# 03-POWER.net
KiCad netlist of a schematic drawn in Altium Designer
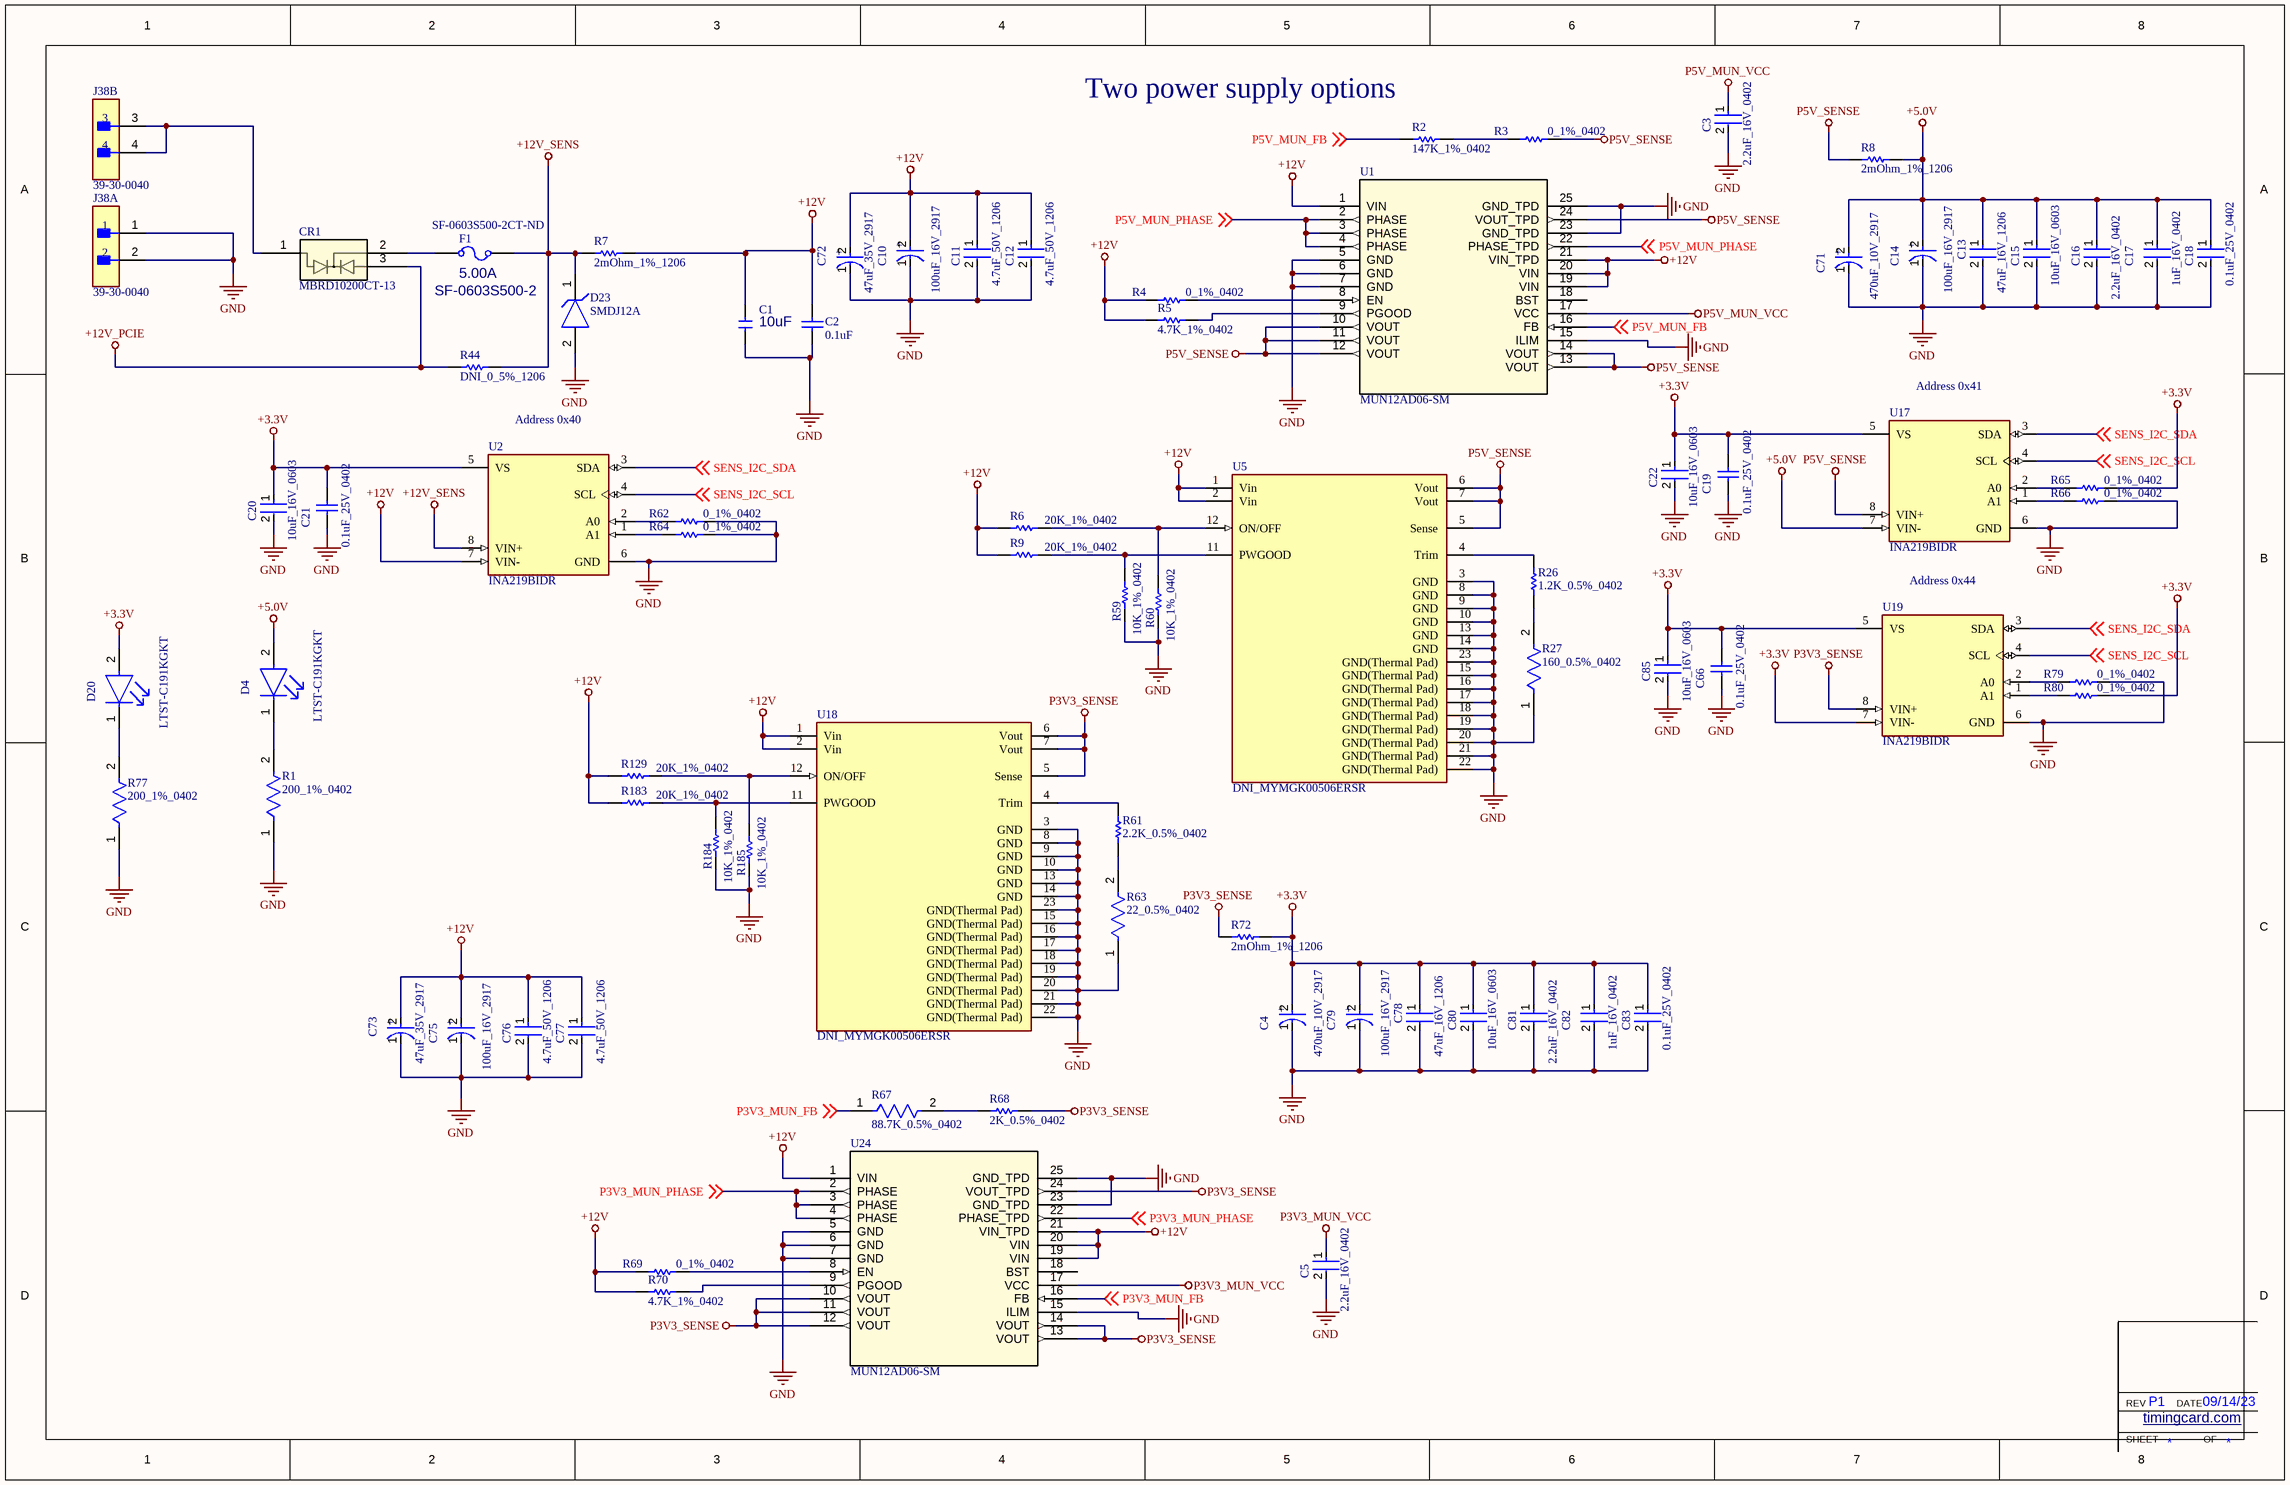
[diagram p0: 03-POWER.SchDoc]

(export (version "E")
  (design (tool "Eeschema 10.0.6"))
  (components
    (comp (ref "C1")
      (value "10uF")
      (footprint "CAPC2012X14N")
      (description "CAP, CER, 10.UF, 25V, 10%, X5R, 0805")
      (fields
        (field (name "MFG PART NUM") "TMK212BBJ106KG-T")
        (field (name "VALENTIUM PART NUM") "<VALENTIUM>")
      )
      (libsource (lib "Capacitors") (part "CAP_0805_10UF_25V"))
    )
    (comp (ref "C2")
      (value "0.1uF")
      (footprint "CAPC1608X87X45ML20T05")
      (description "C0603X104K5RACAUTO")
      (fields (field (name "MANUFACTURER") "Kemet"))
      (libsource (lib "Altium Content Vault") (part "CAP"))
    )
    (comp (ref "C3")
      (value "2.2uF_16V_0402")
      (footprint "FP-C1005-050-0_05-IPC_A")
      (description "Multilayer Ceramic Capacitors 2.2μF ±10% 16V X5R SMD 0402")
      (fields (field (name "TOLERANCE") "10%"))
      (libsource (lib "Altium Content Vault") (part "b4654b650e69147ec39a6b967a45e02"))
    )
    (comp (ref "C4")
      (value "470uF_10V_2917")
      (footprint "FP-TAJE-MFG")
      (description "470uF 10V  ±10% 500mΩ 2917  SMD Tantalum Capacitor")
      (fields (field (name "TOLERANCE") "10%") (field (name "VOLTAGE") "10V"))
      (libsource (lib "Altium Content Vault") (part "203bc49f2ac43e59fd269a8c329ed05"))
    )
    (comp (ref "C5")
      (value "2.2uF_16V_0402")
      (footprint "FP-C1005-050-0_05-IPC_A")
      (description "Multilayer Ceramic Capacitors 2.2μF ±10% 16V X5R SMD 0402")
      (fields (field (name "TOLERANCE") "10%"))
      (libsource (lib "Altium Content Vault") (part "b4654b650e69147ec39a6b967a45e02"))
    )
    (comp (ref "C10")
      (value "100uF_16V_2917")
      (footprint "FP-T495D107K016ATE125-MFG")
      (description "CAP TANT 100UF 10% 16V 2917")
      (fields (field (name "VOLTAGE") "16V") (field (name "TOLERANCE") "10%"))
      (libsource (lib "Altium Content Vault") (part "a00bbbee19879c290e62620ae7e47b1"))
    )
    (comp (ref "C11")
      (value "4.7uF_50V_1206")
      (footprint "FP-GRM31C-0_2-e0_3_0_8-IPC_C")
      (description "Chip Multilayer Ceramic Capacitors for General Purpose, 1206, 4.7uF, X7R, 15%, 10%, 50V")
      (fields (field (name "VOLTAGE") "50V") (field (name "TOLERANCE") "10%"))
      (libsource (lib "Altium Content Vault") (part "02cd4be3c70576c341d710602a673aa"))
    )
    (comp (ref "C12")
      (value "4.7uF_50V_1206")
      (footprint "FP-GRM31C-0_2-e0_3_0_8-IPC_C")
      (description "Chip Multilayer Ceramic Capacitors for General Purpose, 1206, 4.7uF, X7R, 15%, 10%, 50V")
      (fields (field (name "VOLTAGE") "50V") (field (name "TOLERANCE") "10%"))
      (libsource (lib "Altium Content Vault") (part "02cd4be3c70576c341d710602a673aa"))
    )
    (comp (ref "C13")
      (value "47uF_16V_1206")
      (footprint "FP-C3216-160-0_2-MFG")
      (description "Multilayer Ceramic Capacitors 47uF ±20% 16V X5R SMD 1206")
      (fields (field (name "TOLERANCE") "20%"))
      (libsource (lib "Altium Content Vault") (part "11868f565c42a9108669ba33697ecf6"))
    )
    (comp (ref "C14")
      (value "100uF_16V_2917")
      (footprint "FP-T495D107K016ATE125-MFG")
      (description "CAP TANT 100UF 10% 16V 2917")
      (fields (field (name "VOLTAGE") "16V") (field (name "TOLERANCE") "10%"))
      (libsource (lib "Altium Content Vault") (part "a00bbbee19879c290e62620ae7e47b1"))
    )
    (comp (ref "C15")
      (value "10uF_16V_0603")
      (footprint "FP-0603-L_1_6_0_2-W_0_8_0-MFG")
      (description "Multilayer Ceramic Capacitor 10uF 16V X5R 20% SMD 0603 T/R")
      (fields (field (name "TOLERANCE") "20%"))
      (libsource (lib "Altium Content Vault") (part "b4654b650e69147ec39a6b967a45e02"))
    )
    (comp (ref "C16")
      (value "2.2uF_16V_0402")
      (footprint "FP-C1005-050-0_05-IPC_A")
      (description "Multilayer Ceramic Capacitors 2.2μF ±10% 16V X5R SMD 0402")
      (fields (field (name "TOLERANCE") "10%"))
      (libsource (lib "Altium Content Vault") (part "b4654b650e69147ec39a6b967a45e02"))
    )
    (comp (ref "C17")
      (value "1uF_16V_0402")
      (footprint "FP-0402-L_1_0_0_05-W_0_5-IPC_A")
      (description "None")
      (fields (field (name "TOLERANCE") "10%"))
      (libsource (lib "Altium Content Vault") (part "b4654b650e69147ec39a6b967a45e02"))
    )
    (comp (ref "C18")
      (value "0.1uF_25V_0402")
      (footprint "FP-0402-L_1_0_1-W_0_5_0_1-IPC_C")
      (description "General Purpose Ceramic Capacitor, 0402, 100nF, 10%, X7R, 15%, 25V")
      (fields (field (name "VOLTAGE") "25V") (field (name "TOLERANCE") "10%"))
      (libsource (lib "Altium Content Vault") (part "b4654b650e69147ec39a6b967a45e02"))
    )
    (comp (ref "C19")
      (value "0.1uF_25V_0402")
      (footprint "CAPC1005X56X25NL10T15")
      (fields
        (field (name "PART NUMBER") "04023D104KAT2A")
        (field (name "MANUFACTURER") "AVX Interconnect / Elco")
      )
      (libsource (lib "Altium Content Vault") (part "CAP"))
    )
    (comp (ref "C20")
      (value "10uF_16V_0603")
      (footprint "FP-0603-L_1_6_0_2-W_0_8_0-MFG")
      (description "Multilayer Ceramic Capacitor 10uF 16V X5R 20% SMD 0603 T/R")
      (fields (field (name "TOLERANCE") "20%"))
      (libsource (lib "Altium Content Vault") (part "b4654b650e69147ec39a6b967a45e02"))
    )
    (comp (ref "C21")
      (value "0.1uF_25V_0402")
      (footprint "CAPC1005X56X25NL10T15")
      (fields
        (field (name "PART NUMBER") "04023D104KAT2A")
        (field (name "MANUFACTURER") "AVX Interconnect / Elco")
      )
      (libsource (lib "Altium Content Vault") (part "CAP"))
    )
    (comp (ref "C22")
      (value "10uF_16V_0603")
      (footprint "FP-0603-L_1_6_0_2-W_0_8_0-MFG")
      (description "Multilayer Ceramic Capacitor 10uF 16V X5R 20% SMD 0603 T/R")
      (fields (field (name "TOLERANCE") "20%"))
      (libsource (lib "Altium Content Vault") (part "b4654b650e69147ec39a6b967a45e02"))
    )
    (comp (ref "C66")
      (value "0.1uF_25V_0402")
      (footprint "CAPC1005X56X25NL10T15")
      (fields
        (field (name "PART NUMBER") "04023D104KAT2A")
        (field (name "MANUFACTURER") "AVX Interconnect / Elco")
      )
      (libsource (lib "Altium Content Vault") (part "CAP"))
    )
    (comp (ref "C71")
      (value "470uF_10V_2917")
      (footprint "FP-TAJE-MFG")
      (description "470uF 10V  ±10% 500mΩ 2917  SMD Tantalum Capacitor")
      (fields (field (name "TOLERANCE") "10%") (field (name "VOLTAGE") "10V"))
      (libsource (lib "Altium Content Vault") (part "203bc49f2ac43e59fd269a8c329ed05"))
    )
    (comp (ref "C72")
      (value "47uF_35V_2917")
      (footprint "FP-T521X476M035ATE030-MFG")
      (description "CAP TANT POLY 47UF 35V 2917")
      (fields (field (name "TOLERANCE") "20%"))
      (libsource (lib "Altium Content Vault") (part "a00bbbee19879c290e62620ae7e47b1"))
    )
    (comp (ref "C73")
      (value "47uF_35V_2917")
      (footprint "FP-T521X476M035ATE030-MFG")
      (description "CAP TANT POLY 47UF 35V 2917")
      (fields (field (name "TOLERANCE") "20%"))
      (libsource (lib "Altium Content Vault") (part "a00bbbee19879c290e62620ae7e47b1"))
    )
    (comp (ref "C75")
      (value "100uF_16V_2917")
      (footprint "FP-T495D107K016ATE125-MFG")
      (description "CAP TANT 100UF 10% 16V 2917")
      (fields (field (name "VOLTAGE") "16V") (field (name "TOLERANCE") "10%"))
      (libsource (lib "Altium Content Vault") (part "a00bbbee19879c290e62620ae7e47b1"))
    )
    (comp (ref "C76")
      (value "4.7uF_50V_1206")
      (footprint "FP-GRM31C-0_2-e0_3_0_8-IPC_C")
      (description "Chip Multilayer Ceramic Capacitors for General Purpose, 1206, 4.7uF, X7R, 15%, 10%, 50V")
      (fields (field (name "VOLTAGE") "50V") (field (name "TOLERANCE") "10%"))
      (libsource (lib "Altium Content Vault") (part "02cd4be3c70576c341d710602a673aa"))
    )
    (comp (ref "C77")
      (value "4.7uF_50V_1206")
      (footprint "FP-GRM31C-0_2-e0_3_0_8-IPC_C")
      (description "Chip Multilayer Ceramic Capacitors for General Purpose, 1206, 4.7uF, X7R, 15%, 10%, 50V")
      (fields (field (name "VOLTAGE") "50V") (field (name "TOLERANCE") "10%"))
      (libsource (lib "Altium Content Vault") (part "02cd4be3c70576c341d710602a673aa"))
    )
    (comp (ref "C78")
      (value "47uF_16V_1206")
      (footprint "FP-C3216-160-0_2-MFG")
      (description "Multilayer Ceramic Capacitors 47uF ±20% 16V X5R SMD 1206")
      (fields (field (name "TOLERANCE") "20%"))
      (libsource (lib "Altium Content Vault") (part "11868f565c42a9108669ba33697ecf6"))
    )
    (comp (ref "C79")
      (value "100uF_16V_2917")
      (footprint "FP-T495D107K016ATE125-MFG")
      (description "CAP TANT 100UF 10% 16V 2917")
      (fields (field (name "VOLTAGE") "16V") (field (name "TOLERANCE") "10%"))
      (libsource (lib "Altium Content Vault") (part "a00bbbee19879c290e62620ae7e47b1"))
    )
    (comp (ref "C80")
      (value "10uF_16V_0603")
      (footprint "FP-0603-L_1_6_0_2-W_0_8_0-MFG")
      (description "Multilayer Ceramic Capacitor 10uF 16V X5R 20% SMD 0603 T/R")
      (fields (field (name "TOLERANCE") "20%"))
      (libsource (lib "Altium Content Vault") (part "b4654b650e69147ec39a6b967a45e02"))
    )
    (comp (ref "C81")
      (value "2.2uF_16V_0402")
      (footprint "FP-C1005-050-0_05-IPC_A")
      (description "Multilayer Ceramic Capacitors 2.2μF ±10% 16V X5R SMD 0402")
      (fields (field (name "TOLERANCE") "10%"))
      (libsource (lib "Altium Content Vault") (part "b4654b650e69147ec39a6b967a45e02"))
    )
    (comp (ref "C82")
      (value "1uF_16V_0402")
      (footprint "FP-0402-L_1_0_0_05-W_0_5-IPC_A")
      (description "None")
      (fields (field (name "TOLERANCE") "10%"))
      (libsource (lib "Altium Content Vault") (part "b4654b650e69147ec39a6b967a45e02"))
    )
    (comp (ref "C83")
      (value "0.1uF_25V_0402")
      (footprint "FP-0402-L_1_0_1-W_0_5_0_1-IPC_C")
      (description "General Purpose Ceramic Capacitor, 0402, 100nF, 10%, X7R, 15%, 25V")
      (fields (field (name "VOLTAGE") "25V") (field (name "TOLERANCE") "10%"))
      (libsource (lib "Altium Content Vault") (part "b4654b650e69147ec39a6b967a45e02"))
    )
    (comp (ref "C85")
      (value "10uF_16V_0603")
      (footprint "FP-0603-L_1_6_0_2-W_0_8_0-MFG")
      (description "Multilayer Ceramic Capacitor 10uF 16V X5R 20% SMD 0603 T/R")
      (fields (field (name "TOLERANCE") "20%"))
      (libsource (lib "Altium Content Vault") (part "b4654b650e69147ec39a6b967a45e02"))
    )
    (comp (ref "CR1")
      (value "MBRD10200CT-13")
      (footprint "TO252(DPAK)_DIO")
      (description "No Description Available")
      (libsource (lib "MBRD10200CT-13") (part "MBRD10200CT-13"))
    )
    (comp (ref "D4")
      (value "LTST-C191KGKT")
      (footprint "FP-LTST-C191KGKT-MFG")
      (description "LED GREEN CLEAR SMD")
      (libsource (lib "Altium Content Vault") (part "8706943c75ba83719d021d2fdc84c58"))
    )
    (comp (ref "D20")
      (value "LTST-C191KGKT")
      (footprint "FP-LTST-C191KGKT-MFG")
      (description "LED GREEN CLEAR SMD")
      (libsource (lib "Altium Content Vault") (part "8706943c75ba83719d021d2fdc84c58"))
    )
    (comp (ref "D23")
      (value "SMDJ12A")
      (footprint "FP-DO-214AB_SMC_J-Bend-MFG")
      (description "TVS DIODE 12V 19.9V DO214AB")
      (libsource (lib "Altium Content Vault") (part "673ecd2ea4d7fb87b4005b0cb348b7d"))
    )
    (comp (ref "F1")
      (value "5.00A")
      (footprint "FUSM1608X60N")
      (description "FUSE SLOW 5.00A 32V M 0603")
      (fields
        (field (name "MFG PART NUM") "SF-0603S500-2")
        (field (name "VALENTIUM PART NUM") "<VALENTIUM>")
        (field (name "SUPPLIER PART NUMBER 1") "SF-0603S500-2CT-ND")
        (field (name "Comment") "FUSE_0603_5.00A")
      )
      (libsource (lib "Passives") (part "FUSE_0603_2.00A"))
    )
    (comp (ref "J38")
      (value "39-30-0040")
      (footprint "FP-39-30-0040-MFG")
      (description "CONN HEADER R/A 4POS 4.2MM")
      (fields
        (field (name "OCTOPART") "https://octopart.com/39-30-0040-molex-277428")
        (field (name "MANUFACTURER") "Molex")
      )
      (libsource (lib "Altium Content Vault") (part "ac72c5313ea981db199dbd0e8237b04"))
    )
    (comp (ref "R1")
      (value "200_1%_0402")
      (footprint "FP-ERJ2RK-IPC_A")
      (description "RES SMD 200 OHM 1% 1/10W 0402")
      (fields (field (name "TOLERANCE") "1%"))
      (libsource (lib "Altium Content Vault") (part "1029c3af85768c4190bb7ad29bc67b5"))
    )
    (comp (ref "R2")
      (value "147K_1%_0402")
      (footprint "RESC1005X40X25ML05T10")
      (fields (field (name "MANUFACTURER") "Yageo / Phycomp") (field (name "PART NUMBER") "RC0402FR-07147KL"))
      (libsource (lib "Altium Content Vault") (part "RES"))
    )
    (comp (ref "R3")
      (value "0_1%_0402")
      (footprint "RESC1005X40X25LL05T05")
      (description "Chip Resistor, 0 Ohm, 0.1 W, -55 to 155 degC, 0402 (1005 Metric), RoHS, Tape and Reel")
      (fields (field (name "MANUFACTURER") "Panasonic") (field (name "TOLERANCE") "5%"))
      (libsource (lib "Altium Content Vault") (part "RES-2"))
    )
    (comp (ref "R4")
      (value "0_1%_0402")
      (footprint "RESC1005X40X25LL05T05")
      (description "Chip Resistor, 0 Ohm, 0.1 W, -55 to 155 degC, 0402 (1005 Metric), RoHS, Tape and Reel")
      (fields (field (name "MANUFACTURER") "Panasonic") (field (name "TOLERANCE") "5%"))
      (libsource (lib "Altium Content Vault") (part "RES-2"))
    )
    (comp (ref "R5")
      (value "4.7K_1%_0402")
      (footprint "RESC1005X40X25NL10T10")
      (fields (field (name "MANUFACTURER") "Bourns") (field (name "PART NUMBER") "CR0402-FX-4701GLF"))
      (libsource (lib "Altium Content Vault") (part "RES"))
    )
    (comp (ref "R6")
      (value "20K_1%_0402")
      (footprint "RESC1005X40X25NL10T10")
      (fields (field (name "PART NUMBER") "MC00625W0402120K") (field (name "MANUFACTURER") "Multicomp"))
      (libsource (lib "Altium Content Vault") (part "RES"))
    )
    (comp (ref "R7")
      (value "2mOhm_1%_1206")
      (footprint "RESC3216X89X64NL25T25")
      (fields (field (name "MANUFACTURER") "Vishay Dale") (field (name "PART NUMBER") "WSL12062L000FEA18"))
      (libsource (lib "Altium Content Vault") (part "RES"))
    )
    (comp (ref "R8")
      (value "2mOhm_1%_1206")
      (footprint "RESC3216X89X64NL25T25")
      (fields (field (name "MANUFACTURER") "Vishay Dale") (field (name "PART NUMBER") "WSL12062L000FEA18"))
      (libsource (lib "Altium Content Vault") (part "RES"))
    )
    (comp (ref "R9")
      (value "20K_1%_0402")
      (footprint "RESC1005X40X25NL10T10")
      (fields (field (name "PART NUMBER") "MC00625W0402120K") (field (name "MANUFACTURER") "Multicomp"))
      (libsource (lib "Altium Content Vault") (part "RES"))
    )
    (comp (ref "R26")
      (value "1.2K_0.5%_0402")
      (footprint "RESC1005X40X25ML10T10")
      (fields (field (name "PART NUMBER") "ERA-2AED122X") (field (name "MANUFACTURER") "Panasonic"))
      (libsource (lib "Altium Content Vault") (part "RES"))
    )
    (comp (ref "R27")
      (value "160_0.5%_0402")
      (footprint "FP-RT0402-MFG")
      (description "RES SMD 160 OHM 0.5% 1/16W 0402")
      (fields
        (field (name "TOLERANCE") "0.005")
        (field (name "OCTOPART") "https://octopart.com/rt0402dre07160rl-yageo-1216058")
      )
      (libsource (lib "Altium Content Vault") (part "1029c3af85768c4190bb7ad29bc67b5"))
    )
    (comp (ref "R44")
      (value "DNI_0_5%_1206")
      (footprint "RESC3116X65X50ML20T20")
      (fields (field (name "PART NUMBER") "CRCW12060000Z0EAHP") (field (name "MANUFACTURER") "Vishay Dale"))
      (libsource (lib "Altium Content Vault") (part "RES"))
    )
    (comp (ref "R59")
      (value "10K_1%_0402")
      (footprint "RESC1005X40X25NL10T10")
      (fields (field (name "MANUFACTURER") "Bourns") (field (name "PART NUMBER") "CR0402-FX-1002GLF"))
      (libsource (lib "Altium Content Vault") (part "RES"))
    )
    (comp (ref "R60")
      (value "10K_1%_0402")
      (footprint "RESC1005X40X25NL10T10")
      (fields (field (name "MANUFACTURER") "Bourns") (field (name "PART NUMBER") "CR0402-FX-1002GLF"))
      (libsource (lib "Altium Content Vault") (part "RES"))
    )
    (comp (ref "R61")
      (value "2.2K_0.5%_0402")
      (footprint "RESC1005X40X25ML10T10")
      (fields (field (name "PART NUMBER") "ERA-2AED222X") (field (name "MANUFACTURER") "Panasonic"))
      (libsource (lib "Altium Content Vault") (part "RES"))
    )
    (comp (ref "R62")
      (value "0_1%_0402")
      (footprint "RESC1005X40X25LL05T05")
      (description "Chip Resistor, 0 Ohm, 0.1 W, -55 to 155 degC, 0402 (1005 Metric), RoHS, Tape and Reel")
      (fields (field (name "MANUFACTURER") "Panasonic") (field (name "TOLERANCE") "5%"))
      (libsource (lib "Altium Content Vault") (part "RES-2"))
    )
    (comp (ref "R63")
      (value "22_0.5%_0402")
      (footprint "FP-RG1005-IPC_A")
      (description "Automotive Metal Thin Film Chip Resistor, 0402, 22Ω, 0.5%, 100ppm/°C, 0.0625W, 75V")
      (fields (field (name "TOLERANCE") "0.5%"))
      (libsource (lib "Altium Content Vault") (part "1029c3af85768c4190bb7ad29bc67b5"))
    )
    (comp (ref "R64")
      (value "0_1%_0402")
      (footprint "RESC1005X40X25LL05T05")
      (description "Chip Resistor, 0 Ohm, 0.1 W, -55 to 155 degC, 0402 (1005 Metric), RoHS, Tape and Reel")
      (fields (field (name "MANUFACTURER") "Panasonic") (field (name "TOLERANCE") "5%"))
      (libsource (lib "Altium Content Vault") (part "RES-2"))
    )
    (comp (ref "R65")
      (value "0_1%_0402")
      (footprint "RESC1005X40X25LL05T05")
      (description "Chip Resistor, 0 Ohm, 0.1 W, -55 to 155 degC, 0402 (1005 Metric), RoHS, Tape and Reel")
      (fields (field (name "MANUFACTURER") "Panasonic") (field (name "TOLERANCE") "5%"))
      (libsource (lib "Altium Content Vault") (part "RES-2"))
    )
    (comp (ref "R66")
      (value "0_1%_0402")
      (footprint "RESC1005X40X25LL05T05")
      (description "Chip Resistor, 0 Ohm, 0.1 W, -55 to 155 degC, 0402 (1005 Metric), RoHS, Tape and Reel")
      (fields (field (name "MANUFACTURER") "Panasonic") (field (name "TOLERANCE") "5%"))
      (libsource (lib "Altium Content Vault") (part "RES-2"))
    )
    (comp (ref "R67")
      (value "88.7K_0.5%_0402")
      (footprint "FP-RT0402-MFG")
      (description "RES SMD 88.7K OHM 0.5% 1/16W")
      (fields
        (field (name "OCTOPART") "https://octopart.com/rt0402dre0788k7l-yageo-1439224")
        (field (name "MANUFACTURER") "Yageo")
      )
      (libsource (lib "Altium Content Vault") (part "1029c3af85768c4190bb7ad29bc67b5"))
    )
    (comp (ref "R68")
      (value "2K_0.5%_0402")
      (footprint "RESC1005X35X25LL10T10")
      (fields (field (name "PART NUMBER") "RT0402DRD072KL") (field (name "MANUFACTURER") "Yageo"))
      (libsource (lib "Altium Content Vault") (part "RES"))
    )
    (comp (ref "R69")
      (value "0_1%_0402")
      (footprint "RESC1005X40X25LL05T05")
      (description "Chip Resistor, 0 Ohm, 0.1 W, -55 to 155 degC, 0402 (1005 Metric), RoHS, Tape and Reel")
      (fields (field (name "MANUFACTURER") "Panasonic") (field (name "TOLERANCE") "5%"))
      (libsource (lib "Altium Content Vault") (part "RES-2"))
    )
    (comp (ref "R70")
      (value "4.7K_1%_0402")
      (footprint "RESC1005X40X25NL10T10")
      (fields (field (name "MANUFACTURER") "Bourns") (field (name "PART NUMBER") "CR0402-FX-4701GLF"))
      (libsource (lib "Altium Content Vault") (part "RES"))
    )
    (comp (ref "R72")
      (value "2mOhm_1%_1206")
      (footprint "RESC3216X89X64NL25T25")
      (fields (field (name "MANUFACTURER") "Vishay Dale") (field (name "PART NUMBER") "WSL12062L000FEA18"))
      (libsource (lib "Altium Content Vault") (part "RES"))
    )
    (comp (ref "R77")
      (value "200_1%_0402")
      (footprint "FP-ERJ2RK-IPC_A")
      (description "RES SMD 200 OHM 1% 1/10W 0402")
      (fields (field (name "TOLERANCE") "1%"))
      (libsource (lib "Altium Content Vault") (part "1029c3af85768c4190bb7ad29bc67b5"))
    )
    (comp (ref "R79")
      (value "0_1%_0402")
      (footprint "RESC1005X40X25LL05T05")
      (description "Chip Resistor, 0 Ohm, 0.1 W, -55 to 155 degC, 0402 (1005 Metric), RoHS, Tape and Reel")
      (fields (field (name "MANUFACTURER") "Panasonic") (field (name "TOLERANCE") "5%"))
      (libsource (lib "Altium Content Vault") (part "RES-2"))
    )
    (comp (ref "R80")
      (value "0_1%_0402")
      (footprint "RESC1005X40X25LL05T05")
      (description "Chip Resistor, 0 Ohm, 0.1 W, -55 to 155 degC, 0402 (1005 Metric), RoHS, Tape and Reel")
      (fields (field (name "MANUFACTURER") "Panasonic") (field (name "TOLERANCE") "5%"))
      (libsource (lib "Altium Content Vault") (part "RES-2"))
    )
    (comp (ref "R129")
      (value "20K_1%_0402")
      (footprint "RESC1005X40X25NL10T10")
      (fields (field (name "PART NUMBER") "MC00625W0402120K") (field (name "MANUFACTURER") "Multicomp"))
      (libsource (lib "Altium Content Vault") (part "RES"))
    )
    (comp (ref "R183")
      (value "20K_1%_0402")
      (footprint "RESC1005X40X25NL10T10")
      (fields (field (name "PART NUMBER") "MC00625W0402120K") (field (name "MANUFACTURER") "Multicomp"))
      (libsource (lib "Altium Content Vault") (part "RES"))
    )
    (comp (ref "R184")
      (value "10K_1%_0402")
      (footprint "RESC1005X40X25NL10T10")
      (fields (field (name "MANUFACTURER") "Bourns") (field (name "PART NUMBER") "CR0402-FX-1002GLF"))
      (libsource (lib "Altium Content Vault") (part "RES"))
    )
    (comp (ref "R185")
      (value "10K_1%_0402")
      (footprint "RESC1005X40X25NL10T10")
      (fields (field (name "MANUFACTURER") "Bourns") (field (name "PART NUMBER") "CR0402-FX-1002GLF"))
      (libsource (lib "Altium Content Vault") (part "RES"))
    )
    (comp (ref "U1")
      (value "MUN12AD06-SM")
      (footprint "MUN12AD06-SM_CYN")
      (description "No Description Available")
      (libsource (lib "MUN12AD06-SM") (part "MUN12AD06-SM"))
    )
    (comp (ref "U2")
      (value "INA219BIDR")
      (footprint "FP-D0008A-MFG")
      (description "IC MONITOR PWR/CURR BIDIR 8-SOIC")
      (libsource (lib "Altium Content Vault") (part "41cc1aee4cbc9fa2660a15773fa0e79"))
    )
    (comp (ref "U5")
      (value "DNI_MYMGK00506ERSR")
      (footprint "FP-MYMGK-12-MFG")
      (description "DC DC CONVERTER 0.7-5V")
      (libsource (lib "Altium Content Vault") (part "57b8017c1ce60d7b1362a625e7a4ba1"))
    )
    (comp (ref "U17")
      (value "INA219BIDR")
      (footprint "FP-D0008A-MFG")
      (description "IC MONITOR PWR/CURR BIDIR 8-SOIC")
      (libsource (lib "Altium Content Vault") (part "41cc1aee4cbc9fa2660a15773fa0e79"))
    )
    (comp (ref "U18")
      (value "DNI_MYMGK00506ERSR")
      (footprint "FP-MYMGK-12-MFG")
      (description "DC DC CONVERTER 0.7-5V")
      (libsource (lib "Altium Content Vault") (part "57b8017c1ce60d7b1362a625e7a4ba1"))
    )
    (comp (ref "U19")
      (value "INA219BIDR")
      (footprint "FP-D0008A-MFG")
      (description "IC MONITOR PWR/CURR BIDIR 8-SOIC")
      (libsource (lib "Altium Content Vault") (part "41cc1aee4cbc9fa2660a15773fa0e79"))
    )
    (comp (ref "U24")
      (value "MUN12AD06-SM")
      (footprint "MUN12AD06-SM_CYN")
      (description "No Description Available")
      (libsource (lib "MUN12AD06-SM") (part "MUN12AD06-SM"))
    )
  )
  (nets
    (net (code "1") (name "+3.3V") (class "Default")
      (node (ref "C19") (pin "2") (pinfunction "2_2") (pintype "passive"))
      (node (ref "C20") (pin "1") (pinfunction "1_1") (pintype "passive"))
      (node (ref "C21") (pin "2") (pinfunction "2_2") (pintype "passive"))
      (node (ref "C22") (pin "1") (pinfunction "1_1") (pintype "passive"))
      (node (ref "C4") (pin "2") (pinfunction "A_2") (pintype "passive"))
      (node (ref "C66") (pin "2") (pinfunction "2_2") (pintype "passive"))
      (node (ref "C78") (pin "1") (pinfunction "1_1") (pintype "passive"))
      (node (ref "C79") (pin "2") (pinfunction "A_2") (pintype "passive"))
      (node (ref "C80") (pin "1") (pinfunction "1_1") (pintype "passive"))
      (node (ref "C81") (pin "1") (pinfunction "1_1") (pintype "passive"))
      (node (ref "C82") (pin "1") (pinfunction "1_1") (pintype "passive"))
      (node (ref "C83") (pin "1") (pinfunction "1_1") (pintype "passive"))
      (node (ref "C85") (pin "1") (pinfunction "1_1") (pintype "passive"))
      (node (ref "D20") (pin "2") (pinfunction "A_2") (pintype "passive"))
      (node (ref "R65") (pin "2") (pinfunction "2_2") (pintype "passive"))
      (node (ref "R72") (pin "2") (pinfunction "2_2") (pintype "passive"))
      (node (ref "R80") (pin "2") (pinfunction "2_2") (pintype "passive"))
      (node (ref "U17") (pin "5") (pinfunction "VS_5") (pintype "power_in"))
      (node (ref "U19") (pin "5") (pinfunction "VS_5") (pintype "power_in"))
      (node (ref "U19") (pin "7") (pinfunction "VIN-_7") (pintype "input"))
      (node (ref "U2") (pin "5") (pinfunction "VS_5") (pintype "power_in"))
    )
    (net (code "2") (name "+5.0V") (class "Default")
      (node (ref "C13") (pin "1") (pinfunction "1_1") (pintype "passive"))
      (node (ref "C14") (pin "2") (pinfunction "A_2") (pintype "passive"))
      (node (ref "C15") (pin "1") (pinfunction "1_1") (pintype "passive"))
      (node (ref "C16") (pin "1") (pinfunction "1_1") (pintype "passive"))
      (node (ref "C17") (pin "1") (pinfunction "1_1") (pintype "passive"))
      (node (ref "C18") (pin "1") (pinfunction "1_1") (pintype "passive"))
      (node (ref "C71") (pin "2") (pinfunction "A_2") (pintype "passive"))
      (node (ref "D4") (pin "2") (pinfunction "A_2") (pintype "passive"))
      (node (ref "R8") (pin "2") (pinfunction "2_2") (pintype "passive"))
      (node (ref "U17") (pin "7") (pinfunction "VIN-_7") (pintype "input"))
    )
    (net (code "3") (name "+12V") (class "Default")
      (node (ref "C1") (pin "1") (pinfunction "1_1") (pintype "passive"))
      (node (ref "C10") (pin "2") (pinfunction "A_2") (pintype "passive"))
      (node (ref "C11") (pin "1") (pinfunction "1_1") (pintype "passive"))
      (node (ref "C12") (pin "1") (pinfunction "1_1") (pintype "passive"))
      (node (ref "C2") (pin "2") (pinfunction "2_2") (pintype "passive"))
      (node (ref "C72") (pin "2") (pinfunction "A_2") (pintype "passive"))
      (node (ref "C73") (pin "2") (pinfunction "A_2") (pintype "passive"))
      (node (ref "C75") (pin "2") (pinfunction "A_2") (pintype "passive"))
      (node (ref "C76") (pin "1") (pinfunction "1_1") (pintype "passive"))
      (node (ref "C77") (pin "1") (pinfunction "1_1") (pintype "passive"))
      (node (ref "R129") (pin "1") (pinfunction "1_1") (pintype "passive"))
      (node (ref "R183") (pin "1") (pinfunction "1_1") (pintype "passive"))
      (node (ref "R4") (pin "1") (pinfunction "1_1") (pintype "passive"))
      (node (ref "R5") (pin "2") (pinfunction "2_2") (pintype "passive"))
      (node (ref "R6") (pin "1") (pinfunction "1_1") (pintype "passive"))
      (node (ref "R69") (pin "1") (pinfunction "1_1") (pintype "passive"))
      (node (ref "R7") (pin "2") (pinfunction "2_2") (pintype "passive"))
      (node (ref "R70") (pin "2") (pinfunction "2_2") (pintype "passive"))
      (node (ref "R9") (pin "1") (pinfunction "1_1") (pintype "passive"))
      (node (ref "U1") (pin "1") (pinfunction "VIN_1") (pintype "power_in"))
      (node (ref "U1") (pin "19") (pinfunction "VIN_19") (pintype "power_in"))
      (node (ref "U1") (pin "20") (pinfunction "VIN_20") (pintype "power_in"))
      (node (ref "U1") (pin "21") (pinfunction "VIN_TPD_21") (pintype "power_in"))
      (node (ref "U18") (pin "1") (pinfunction "Vin_1") (pintype "power_in"))
      (node (ref "U18") (pin "2") (pinfunction "Vin_2") (pintype "power_in"))
      (node (ref "U2") (pin "7") (pinfunction "VIN-_7") (pintype "input"))
      (node (ref "U24") (pin "1") (pinfunction "VIN_1") (pintype "power_in"))
      (node (ref "U24") (pin "19") (pinfunction "VIN_19") (pintype "power_in"))
      (node (ref "U24") (pin "20") (pinfunction "VIN_20") (pintype "power_in"))
      (node (ref "U24") (pin "21") (pinfunction "VIN_TPD_21") (pintype "power_in"))
      (node (ref "U5") (pin "1") (pinfunction "Vin_1") (pintype "power_in"))
      (node (ref "U5") (pin "2") (pinfunction "Vin_2") (pintype "power_in"))
    )
    (net (code "4") (name "+12V_PCIE") (class "Default")
      (node (ref "CR1") (pin "3") (pinfunction "3_3") (pintype "passive"))
      (node (ref "R44") (pin "1") (pinfunction "1_1") (pintype "passive"))
    )
    (net (code "5") (name "+12V_SENS") (class "Default")
      (node (ref "D23") (pin "1") (pinfunction "C_1") (pintype "passive"))
      (node (ref "F1") (pin "2") (pinfunction "2_2") (pintype "passive"))
      (node (ref "R44") (pin "2") (pinfunction "2_2") (pintype "passive"))
      (node (ref "R7") (pin "1") (pinfunction "1_1") (pintype "passive"))
      (node (ref "U2") (pin "8") (pinfunction "VIN+_8") (pintype "input"))
    )
    (net (code "6") (name "GND") (class "Default")
      (node (ref "C1") (pin "2") (pinfunction "2_2") (pintype "passive"))
      (node (ref "C10") (pin "1") (pinfunction "C_1") (pintype "passive"))
      (node (ref "C11") (pin "2") (pinfunction "2_2") (pintype "passive"))
      (node (ref "C12") (pin "2") (pinfunction "2_2") (pintype "passive"))
      (node (ref "C13") (pin "2") (pinfunction "2_2") (pintype "passive"))
      (node (ref "C14") (pin "1") (pinfunction "C_1") (pintype "passive"))
      (node (ref "C15") (pin "2") (pinfunction "2_2") (pintype "passive"))
      (node (ref "C16") (pin "2") (pinfunction "2_2") (pintype "passive"))
      (node (ref "C17") (pin "2") (pinfunction "2_2") (pintype "passive"))
      (node (ref "C18") (pin "2") (pinfunction "2_2") (pintype "passive"))
      (node (ref "C19") (pin "1") (pinfunction "1_1") (pintype "passive"))
      (node (ref "C2") (pin "1") (pinfunction "1_1") (pintype "passive"))
      (node (ref "C20") (pin "2") (pinfunction "2_2") (pintype "passive"))
      (node (ref "C21") (pin "1") (pinfunction "1_1") (pintype "passive"))
      (node (ref "C22") (pin "2") (pinfunction "2_2") (pintype "passive"))
      (node (ref "C3") (pin "2") (pinfunction "2_2") (pintype "passive"))
      (node (ref "C4") (pin "1") (pinfunction "C_1") (pintype "passive"))
      (node (ref "C5") (pin "2") (pinfunction "2_2") (pintype "passive"))
      (node (ref "C66") (pin "1") (pinfunction "1_1") (pintype "passive"))
      (node (ref "C71") (pin "1") (pinfunction "C_1") (pintype "passive"))
      (node (ref "C72") (pin "1") (pinfunction "C_1") (pintype "passive"))
      (node (ref "C73") (pin "1") (pinfunction "C_1") (pintype "passive"))
      (node (ref "C75") (pin "1") (pinfunction "C_1") (pintype "passive"))
      (node (ref "C76") (pin "2") (pinfunction "2_2") (pintype "passive"))
      (node (ref "C77") (pin "2") (pinfunction "2_2") (pintype "passive"))
      (node (ref "C78") (pin "2") (pinfunction "2_2") (pintype "passive"))
      (node (ref "C79") (pin "1") (pinfunction "C_1") (pintype "passive"))
      (node (ref "C80") (pin "2") (pinfunction "2_2") (pintype "passive"))
      (node (ref "C81") (pin "2") (pinfunction "2_2") (pintype "passive"))
      (node (ref "C82") (pin "2") (pinfunction "2_2") (pintype "passive"))
      (node (ref "C83") (pin "2") (pinfunction "2_2") (pintype "passive"))
      (node (ref "C85") (pin "2") (pinfunction "2_2") (pintype "passive"))
      (node (ref "D23") (pin "2") (pinfunction "A_2") (pintype "passive"))
      (node (ref "J38") (pin "1") (pinfunction "1_1") (pintype "passive"))
      (node (ref "J38") (pin "2") (pinfunction "2_2") (pintype "passive"))
      (node (ref "R1") (pin "1") (pinfunction "1_1") (pintype "passive"))
      (node (ref "R184") (pin "1") (pinfunction "1_1") (pintype "passive"))
      (node (ref "R185") (pin "1") (pinfunction "1_1") (pintype "passive"))
      (node (ref "R27") (pin "1") (pinfunction "1_1") (pintype "passive"))
      (node (ref "R59") (pin "1") (pinfunction "1_1") (pintype "passive"))
      (node (ref "R60") (pin "1") (pinfunction "1_1") (pintype "passive"))
      (node (ref "R62") (pin "2") (pinfunction "2_2") (pintype "passive"))
      (node (ref "R63") (pin "1") (pinfunction "1_1") (pintype "passive"))
      (node (ref "R64") (pin "2") (pinfunction "2_2") (pintype "passive"))
      (node (ref "R66") (pin "2") (pinfunction "2_2") (pintype "passive"))
      (node (ref "R77") (pin "1") (pinfunction "1_1") (pintype "passive"))
      (node (ref "R79") (pin "2") (pinfunction "2_2") (pintype "passive"))
      (node (ref "U1") (pin "15") (pinfunction "ILIM_15") (pintype "passive"))
      (node (ref "U1") (pin "23") (pinfunction "GND_TPD_23") (pintype "power_in"))
      (node (ref "U1") (pin "25") (pinfunction "GND_TPD_25") (pintype "power_in"))
      (node (ref "U1") (pin "5") (pinfunction "GND_5") (pintype "power_in"))
      (node (ref "U1") (pin "6") (pinfunction "GND_6") (pintype "power_in"))
      (node (ref "U1") (pin "7") (pinfunction "GND_7") (pintype "power_in"))
      (node (ref "U17") (pin "6") (pinfunction "GND_6") (pintype "power_in"))
      (node (ref "U18") (pin "10") (pinfunction "GND_10") (pintype "power_in"))
      (node (ref "U18") (pin "13") (pinfunction "GND_13") (pintype "power_in"))
      (node (ref "U18") (pin "14") (pinfunction "GND_14") (pintype "power_in"))
      (node (ref "U18") (pin "15") (pinfunction "GND(Thermal_Pad)_15") (pintype "power_in"))
      (node (ref "U18") (pin "16") (pinfunction "GND(Thermal_Pad)_16") (pintype "power_in"))
      (node (ref "U18") (pin "17") (pinfunction "GND(Thermal_Pad)_17") (pintype "power_in"))
      (node (ref "U18") (pin "18") (pinfunction "GND(Thermal_Pad)_18") (pintype "power_in"))
      (node (ref "U18") (pin "19") (pinfunction "GND(Thermal_Pad)_19") (pintype "power_in"))
      (node (ref "U18") (pin "20") (pinfunction "GND(Thermal_Pad)_20") (pintype "power_in"))
      (node (ref "U18") (pin "21") (pinfunction "GND(Thermal_Pad)_21") (pintype "power_in"))
      (node (ref "U18") (pin "22") (pinfunction "GND(Thermal_Pad)_22") (pintype "power_in"))
      (node (ref "U18") (pin "23") (pinfunction "GND(Thermal_Pad)_23") (pintype "power_in"))
      (node (ref "U18") (pin "3") (pinfunction "GND_3") (pintype "power_in"))
      (node (ref "U18") (pin "8") (pinfunction "GND_8") (pintype "power_in"))
      (node (ref "U18") (pin "9") (pinfunction "GND_9") (pintype "power_in"))
      (node (ref "U19") (pin "6") (pinfunction "GND_6") (pintype "power_in"))
      (node (ref "U2") (pin "6") (pinfunction "GND_6") (pintype "power_in"))
      (node (ref "U24") (pin "15") (pinfunction "ILIM_15") (pintype "passive"))
      (node (ref "U24") (pin "23") (pinfunction "GND_TPD_23") (pintype "power_in"))
      (node (ref "U24") (pin "25") (pinfunction "GND_TPD_25") (pintype "power_in"))
      (node (ref "U24") (pin "5") (pinfunction "GND_5") (pintype "power_in"))
      (node (ref "U24") (pin "6") (pinfunction "GND_6") (pintype "power_in"))
      (node (ref "U24") (pin "7") (pinfunction "GND_7") (pintype "power_in"))
      (node (ref "U5") (pin "10") (pinfunction "GND_10") (pintype "power_in"))
      (node (ref "U5") (pin "13") (pinfunction "GND_13") (pintype "power_in"))
      (node (ref "U5") (pin "14") (pinfunction "GND_14") (pintype "power_in"))
      (node (ref "U5") (pin "15") (pinfunction "GND(Thermal_Pad)_15") (pintype "power_in"))
      (node (ref "U5") (pin "16") (pinfunction "GND(Thermal_Pad)_16") (pintype "power_in"))
      (node (ref "U5") (pin "17") (pinfunction "GND(Thermal_Pad)_17") (pintype "power_in"))
      (node (ref "U5") (pin "18") (pinfunction "GND(Thermal_Pad)_18") (pintype "power_in"))
      (node (ref "U5") (pin "19") (pinfunction "GND(Thermal_Pad)_19") (pintype "power_in"))
      (node (ref "U5") (pin "20") (pinfunction "GND(Thermal_Pad)_20") (pintype "power_in"))
      (node (ref "U5") (pin "21") (pinfunction "GND(Thermal_Pad)_21") (pintype "power_in"))
      (node (ref "U5") (pin "22") (pinfunction "GND(Thermal_Pad)_22") (pintype "power_in"))
      (node (ref "U5") (pin "23") (pinfunction "GND(Thermal_Pad)_23") (pintype "power_in"))
      (node (ref "U5") (pin "3") (pinfunction "GND_3") (pintype "power_in"))
      (node (ref "U5") (pin "8") (pinfunction "GND_8") (pintype "power_in"))
      (node (ref "U5") (pin "9") (pinfunction "GND_9") (pintype "power_in"))
    )
    (net (code "7") (name "Net-(CR1-Pad1)") (class "Default")
      (node (ref "CR1") (pin "1") (pinfunction "1_1") (pintype "passive"))
      (node (ref "J38") (pin "3") (pinfunction "3_3") (pintype "passive"))
      (node (ref "J38") (pin "4") (pinfunction "4_4") (pintype "passive"))
    )
    (net (code "8") (name "Net-(CR1-Pad2)") (class "Default")
      (node (ref "CR1") (pin "2") (pinfunction "2_2") (pintype "passive"))
      (node (ref "F1") (pin "1") (pinfunction "1_1") (pintype "passive"))
    )
    (net (code "9") (name "Net-(D4-C)") (class "Default")
      (node (ref "D4") (pin "1") (pinfunction "C_1") (pintype "passive"))
      (node (ref "R1") (pin "2") (pinfunction "2_2") (pintype "passive"))
    )
    (net (code "10") (name "Net-(D20-C)") (class "Default")
      (node (ref "D20") (pin "1") (pinfunction "C_1") (pintype "passive"))
      (node (ref "R77") (pin "2") (pinfunction "2_2") (pintype "passive"))
    )
    (net (code "11") (name "Net-(R2-Pad2)") (class "Default")
      (node (ref "R2") (pin "2") (pinfunction "2_2") (pintype "passive"))
      (node (ref "R3") (pin "1") (pinfunction "1_1") (pintype "passive"))
    )
    (net (code "12") (name "Net-(R26-Pad1)") (class "Default")
      (node (ref "R26") (pin "1") (pinfunction "1_1") (pintype "passive"))
      (node (ref "R27") (pin "2") (pinfunction "2_2") (pintype "passive"))
    )
    (net (code "13") (name "Net-(R61-Pad1)") (class "Default")
      (node (ref "R61") (pin "1") (pinfunction "1_1") (pintype "passive"))
      (node (ref "R63") (pin "2") (pinfunction "2_2") (pintype "passive"))
    )
    (net (code "14") (name "Net-(R67-Pad2)") (class "Default")
      (node (ref "R67") (pin "2") (pinfunction "2_2") (pintype "passive"))
      (node (ref "R68") (pin "1") (pinfunction "1_1") (pintype "passive"))
    )
    (net (code "15") (name "Net-(U1-EN)") (class "Default")
      (node (ref "R4") (pin "2") (pinfunction "2_2") (pintype "passive"))
      (node (ref "U1") (pin "8") (pinfunction "EN_8") (pintype "input"))
    )
    (net (code "16") (name "Net-(U1-PGOOD)") (class "Default")
      (node (ref "R5") (pin "1") (pinfunction "1_1") (pintype "passive"))
      (node (ref "U1") (pin "9") (pinfunction "PGOOD_9") (pintype "output"))
    )
    (net (code "17") (name "Net-(U2-A0)") (class "Default")
      (node (ref "R62") (pin "1") (pinfunction "1_1") (pintype "passive"))
      (node (ref "U2") (pin "2") (pinfunction "A0_2") (pintype "input"))
    )
    (net (code "18") (name "Net-(U2-A1)") (class "Default")
      (node (ref "R64") (pin "1") (pinfunction "1_1") (pintype "passive"))
      (node (ref "U2") (pin "1") (pinfunction "A1_1") (pintype "input"))
    )
    (net (code "19") (name "Net-(U5-ON{slash}OFF)") (class "Default")
      (node (ref "R6") (pin "2") (pinfunction "2_2") (pintype "passive"))
      (node (ref "R60") (pin "2") (pinfunction "2_2") (pintype "passive"))
      (node (ref "U5") (pin "12") (pinfunction "ON/OFF_12") (pintype "input"))
    )
    (net (code "20") (name "Net-(U5-PWGOOD)") (class "Default")
      (node (ref "R59") (pin "2") (pinfunction "2_2") (pintype "passive"))
      (node (ref "R9") (pin "2") (pinfunction "2_2") (pintype "passive"))
      (node (ref "U5") (pin "11") (pinfunction "PWGOOD_11") (pintype "open_collector"))
    )
    (net (code "21") (name "Net-(U5-Trim)") (class "Default")
      (node (ref "R26") (pin "2") (pinfunction "2_2") (pintype "passive"))
      (node (ref "U5") (pin "4") (pinfunction "Trim_4") (pintype "passive"))
    )
    (net (code "22") (name "Net-(U17-A0)") (class "Default")
      (node (ref "R65") (pin "1") (pinfunction "1_1") (pintype "passive"))
      (node (ref "U17") (pin "2") (pinfunction "A0_2") (pintype "input"))
    )
    (net (code "23") (name "Net-(U17-A1)") (class "Default")
      (node (ref "R66") (pin "1") (pinfunction "1_1") (pintype "passive"))
      (node (ref "U17") (pin "1") (pinfunction "A1_1") (pintype "input"))
    )
    (net (code "24") (name "Net-(U18-ON{slash}OFF)") (class "Default")
      (node (ref "R129") (pin "2") (pinfunction "2_2") (pintype "passive"))
      (node (ref "R185") (pin "2") (pinfunction "2_2") (pintype "passive"))
      (node (ref "U18") (pin "12") (pinfunction "ON/OFF_12") (pintype "input"))
    )
    (net (code "25") (name "Net-(U18-PWGOOD)") (class "Default")
      (node (ref "R183") (pin "2") (pinfunction "2_2") (pintype "passive"))
      (node (ref "R184") (pin "2") (pinfunction "2_2") (pintype "passive"))
      (node (ref "U18") (pin "11") (pinfunction "PWGOOD_11") (pintype "open_collector"))
    )
    (net (code "26") (name "Net-(U18-Trim)") (class "Default")
      (node (ref "R61") (pin "2") (pinfunction "2_2") (pintype "passive"))
      (node (ref "U18") (pin "4") (pinfunction "Trim_4") (pintype "passive"))
    )
    (net (code "27") (name "Net-(U19-A0)") (class "Default")
      (node (ref "R79") (pin "1") (pinfunction "1_1") (pintype "passive"))
      (node (ref "U19") (pin "2") (pinfunction "A0_2") (pintype "input"))
    )
    (net (code "28") (name "Net-(U19-A1)") (class "Default")
      (node (ref "R80") (pin "1") (pinfunction "1_1") (pintype "passive"))
      (node (ref "U19") (pin "1") (pinfunction "A1_1") (pintype "input"))
    )
    (net (code "29") (name "Net-(U24-EN)") (class "Default")
      (node (ref "R69") (pin "2") (pinfunction "2_2") (pintype "passive"))
      (node (ref "U24") (pin "8") (pinfunction "EN_8") (pintype "input"))
    )
    (net (code "30") (name "Net-(U24-PGOOD)") (class "Default")
      (node (ref "R70") (pin "1") (pinfunction "1_1") (pintype "passive"))
      (node (ref "U24") (pin "9") (pinfunction "PGOOD_9") (pintype "output"))
    )
    (net (code "31") (name "P3V3_MUN_FB") (class "Default")
      (node (ref "R67") (pin "1") (pinfunction "1_1") (pintype "passive"))
      (node (ref "U24") (pin "16") (pinfunction "FB_16") (pintype "input"))
    )
    (net (code "32") (name "P3V3_MUN_PHASE") (class "Default")
      (node (ref "U24") (pin "2") (pinfunction "PHASE_2") (pintype "output"))
      (node (ref "U24") (pin "22") (pinfunction "PHASE_TPD_22") (pintype "output"))
      (node (ref "U24") (pin "3") (pinfunction "PHASE_3") (pintype "output"))
      (node (ref "U24") (pin "4") (pinfunction "PHASE_4") (pintype "output"))
    )
    (net (code "33") (name "P3V3_MUN_VCC") (class "Default")
      (node (ref "C5") (pin "1") (pinfunction "1_1") (pintype "passive"))
      (node (ref "U24") (pin "17") (pinfunction "VCC_17") (pintype "power_in"))
    )
    (net (code "34") (name "P3V3_SENSE") (class "Default")
      (node (ref "R68") (pin "2") (pinfunction "2_2") (pintype "passive"))
      (node (ref "R72") (pin "1") (pinfunction "1_1") (pintype "passive"))
      (node (ref "U18") (pin "5") (pinfunction "Sense_5") (pintype "passive"))
      (node (ref "U18") (pin "6") (pinfunction "Vout_6") (pintype "power_in"))
      (node (ref "U18") (pin "7") (pinfunction "Vout_7") (pintype "power_in"))
      (node (ref "U19") (pin "8") (pinfunction "VIN+_8") (pintype "input"))
      (node (ref "U24") (pin "10") (pinfunction "VOUT_10") (pintype "output"))
      (node (ref "U24") (pin "11") (pinfunction "VOUT_11") (pintype "output"))
      (node (ref "U24") (pin "12") (pinfunction "VOUT_12") (pintype "output"))
      (node (ref "U24") (pin "13") (pinfunction "VOUT_13") (pintype "output"))
      (node (ref "U24") (pin "14") (pinfunction "VOUT_14") (pintype "output"))
      (node (ref "U24") (pin "24") (pinfunction "VOUT_TPD_24") (pintype "output"))
    )
    (net (code "35") (name "P5V_MUN_FB") (class "Default")
      (node (ref "R2") (pin "1") (pinfunction "1_1") (pintype "passive"))
      (node (ref "U1") (pin "16") (pinfunction "FB_16") (pintype "input"))
    )
    (net (code "36") (name "P5V_MUN_PHASE") (class "Default")
      (node (ref "U1") (pin "2") (pinfunction "PHASE_2") (pintype "output"))
      (node (ref "U1") (pin "22") (pinfunction "PHASE_TPD_22") (pintype "output"))
      (node (ref "U1") (pin "3") (pinfunction "PHASE_3") (pintype "output"))
      (node (ref "U1") (pin "4") (pinfunction "PHASE_4") (pintype "output"))
    )
    (net (code "37") (name "P5V_MUN_VCC") (class "Default")
      (node (ref "C3") (pin "1") (pinfunction "1_1") (pintype "passive"))
      (node (ref "U1") (pin "17") (pinfunction "VCC_17") (pintype "power_in"))
    )
    (net (code "38") (name "P5V_SENSE") (class "Default")
      (node (ref "R3") (pin "2") (pinfunction "2_2") (pintype "passive"))
      (node (ref "R8") (pin "1") (pinfunction "1_1") (pintype "passive"))
      (node (ref "U1") (pin "10") (pinfunction "VOUT_10") (pintype "output"))
      (node (ref "U1") (pin "11") (pinfunction "VOUT_11") (pintype "output"))
      (node (ref "U1") (pin "12") (pinfunction "VOUT_12") (pintype "output"))
      (node (ref "U1") (pin "13") (pinfunction "VOUT_13") (pintype "output"))
      (node (ref "U1") (pin "14") (pinfunction "VOUT_14") (pintype "output"))
      (node (ref "U1") (pin "24") (pinfunction "VOUT_TPD_24") (pintype "output"))
      (node (ref "U17") (pin "8") (pinfunction "VIN+_8") (pintype "input"))
      (node (ref "U5") (pin "5") (pinfunction "Sense_5") (pintype "passive"))
      (node (ref "U5") (pin "6") (pinfunction "Vout_6") (pintype "power_in"))
      (node (ref "U5") (pin "7") (pinfunction "Vout_7") (pintype "power_in"))
    )
    (net (code "39") (name "SENS_I2C_SCL") (class "Default")
      (node (ref "U17") (pin "4") (pinfunction "SCL_4") (pintype "bidirectional"))
      (node (ref "U19") (pin "4") (pinfunction "SCL_4") (pintype "bidirectional"))
      (node (ref "U2") (pin "4") (pinfunction "SCL_4") (pintype "bidirectional"))
    )
    (net (code "40") (name "SENS_I2C_SDA") (class "Default")
      (node (ref "U17") (pin "3") (pinfunction "SDA_3") (pintype "bidirectional"))
      (node (ref "U19") (pin "3") (pinfunction "SDA_3") (pintype "bidirectional"))
      (node (ref "U2") (pin "3") (pinfunction "SDA_3") (pintype "bidirectional"))
    )
    (net (code "41") (name "unconnected-(U1-BST-Pad18)") (class "Default")
      (node (ref "U1") (pin "18") (pinfunction "BST_18") (pintype "power_in"))
    )
    (net (code "42") (name "unconnected-(U24-BST-Pad18)") (class "Default")
      (node (ref "U24") (pin "18") (pinfunction "BST_18") (pintype "power_in"))
    )
  )
)
